# Adafruit_Bluefruit_LE_USB_Friend_Rev_I.net
KiCad netlist of a schematic drawn in EAGLE
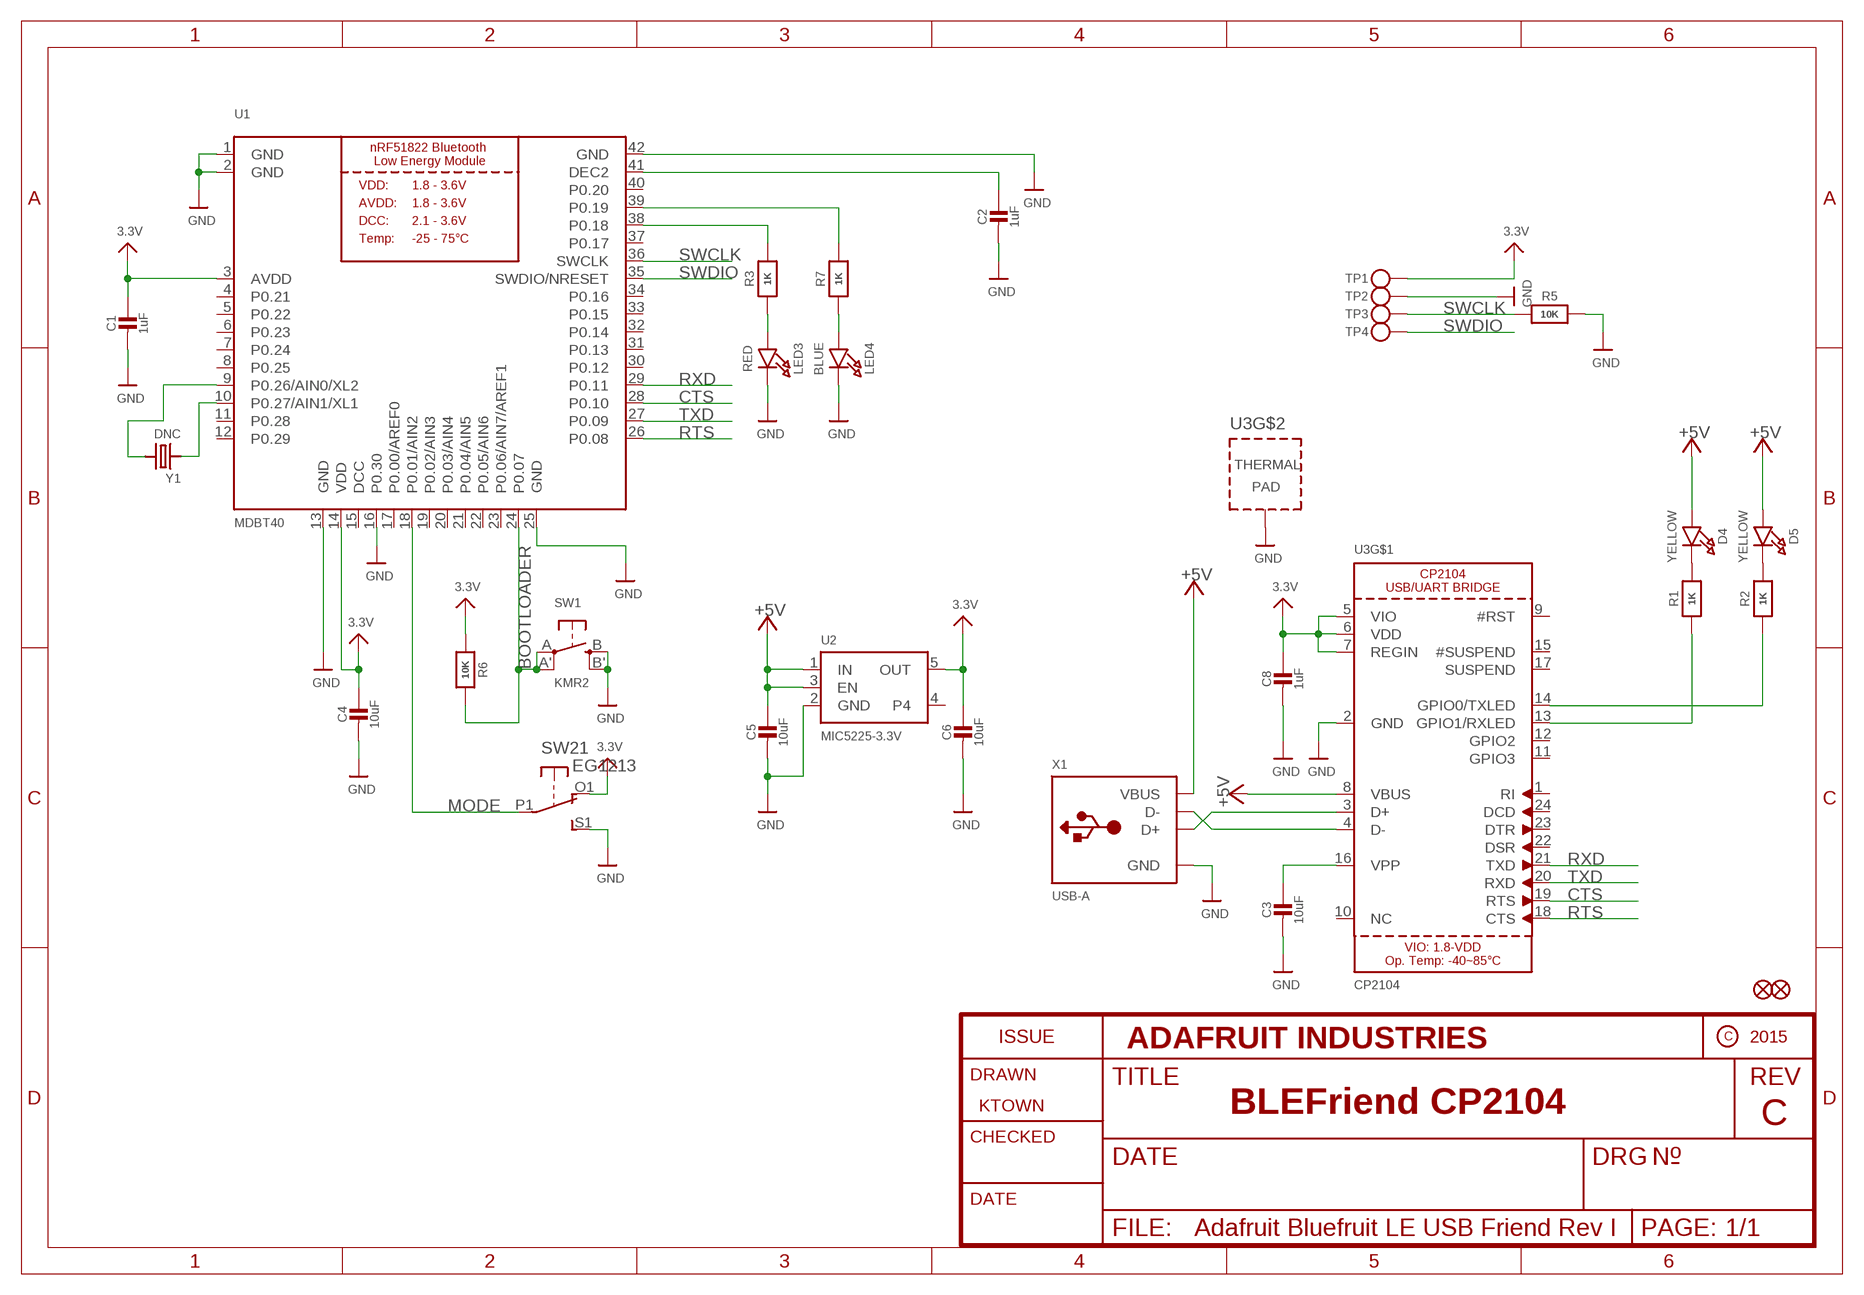
[diagram p0: schematic, sheet 1]

(export (version "E")
  (design (tool "Eeschema 10.0.6"))
  (components
    (comp (ref "C1")
      (value "1uF")
      (footprint "eagle-import:0805-NO")
      (libsource (lib "eagle-import") (part "CAP_CERAMIC0805-NOOUTLINE"))
    )
    (comp (ref "C2")
      (value "1uF")
      (footprint "eagle-import:0805-NO")
      (libsource (lib "eagle-import") (part "CAP_CERAMIC0805-NOOUTLINE"))
    )
    (comp (ref "C3")
      (value "10uF")
      (footprint "eagle-import:0805-NO")
      (libsource (lib "eagle-import") (part "CAP_CERAMIC0805-NOOUTLINE"))
    )
    (comp (ref "C4")
      (value "10uF")
      (footprint "eagle-import:0805-NO")
      (libsource (lib "eagle-import") (part "CAP_CERAMIC0805-NOOUTLINE"))
    )
    (comp (ref "C5")
      (value "10uF")
      (footprint "eagle-import:0805-NO")
      (libsource (lib "eagle-import") (part "CAP_CERAMIC0805-NOOUTLINE"))
    )
    (comp (ref "C6")
      (value "10uF")
      (footprint "eagle-import:0805-NO")
      (libsource (lib "eagle-import") (part "CAP_CERAMIC0805-NOOUTLINE"))
    )
    (comp (ref "C8")
      (value "1uF")
      (footprint "eagle-import:0805-NO")
      (libsource (lib "eagle-import") (part "CAP_CERAMIC0805-NOOUTLINE"))
    )
    (comp (ref "D4")
      (value "YELLOW")
      (footprint "eagle-import:CHIPLED_0805_NOOUTLINE")
      (libsource (lib "eagle-import") (part "LED0805_NOOUTLINE"))
    )
    (comp (ref "D5")
      (value "YELLOW")
      (footprint "eagle-import:CHIPLED_0805_NOOUTLINE")
      (libsource (lib "eagle-import") (part "LED0805_NOOUTLINE"))
    )
    (comp (ref "FID1")
      (value "FIDUCIAL\"\"")
      (footprint "eagle-import:FIDUCIAL_1MM")
      (libsource (lib "eagle-import") (part "FIDUCIAL{dblquote}{dblquote}"))
    )
    (comp (ref "FID2")
      (value "FIDUCIAL\"\"")
      (footprint "eagle-import:FIDUCIAL_1MM")
      (libsource (lib "eagle-import") (part "FIDUCIAL{dblquote}{dblquote}"))
    )
    (comp (ref "LED3")
      (value "RED")
      (footprint "eagle-import:CHIPLED_0805_NOOUTLINE")
      (libsource (lib "eagle-import") (part "LED0805_NOOUTLINE"))
    )
    (comp (ref "LED4")
      (value "BLUE")
      (footprint "eagle-import:CHIPLED_0805_NOOUTLINE")
      (libsource (lib "eagle-import") (part "LED0805_NOOUTLINE"))
    )
    (comp (ref "R1")
      (value "1K")
      (footprint "eagle-import:0805-NO")
      (libsource (lib "eagle-import") (part "RESISTOR0805_NOOUTLINE"))
    )
    (comp (ref "R2")
      (value "1K")
      (footprint "eagle-import:0805-NO")
      (libsource (lib "eagle-import") (part "RESISTOR0805_NOOUTLINE"))
    )
    (comp (ref "R3")
      (value "1K")
      (footprint "eagle-import:0805_10MGAP")
      (libsource (lib "eagle-import") (part "RESISTOR0805_10MGAP"))
    )
    (comp (ref "R5")
      (value "10K")
      (footprint "eagle-import:0805-NO")
      (libsource (lib "eagle-import") (part "RESISTOR0805_NOOUTLINE"))
    )
    (comp (ref "R6")
      (value "10K")
      (footprint "eagle-import:0805-NO")
      (libsource (lib "eagle-import") (part "RESISTOR0805_NOOUTLINE"))
    )
    (comp (ref "R7")
      (value "1K")
      (footprint "eagle-import:_0805MP")
      (libsource (lib "eagle-import") (part "RESISTOR_0805MP"))
    )
    (comp (ref "SW1")
      (value "KMR2")
      (footprint "eagle-import:BTN_KMR2_4.6X2.8")
      (libsource (lib "eagle-import") (part "SWITCH_TACT_SMT4.6X2.8"))
    )
    (comp (ref "SW2")
      (value "EG1213")
      (footprint "eagle-import:EG1390")
      (libsource (lib "eagle-import") (part "DPDT-EG1390"))
    )
    (comp (ref "TP1")
      (value "TESTPOINTROUND2MM")
      (footprint "eagle-import:TESTPOINT_ROUND_2MM")
      (libsource (lib "eagle-import") (part "TESTPOINTROUND2MM"))
    )
    (comp (ref "TP2")
      (value "TESTPOINTROUND2MM")
      (footprint "eagle-import:TESTPOINT_ROUND_2MM")
      (libsource (lib "eagle-import") (part "TESTPOINTROUND2MM"))
    )
    (comp (ref "TP3")
      (value "TESTPOINTROUND2MM")
      (footprint "eagle-import:TESTPOINT_ROUND_2MM")
      (libsource (lib "eagle-import") (part "TESTPOINTROUND2MM"))
    )
    (comp (ref "TP4")
      (value "TESTPOINTROUND2MM")
      (footprint "eagle-import:TESTPOINT_ROUND_2MM")
      (libsource (lib "eagle-import") (part "TESTPOINTROUND2MM"))
    )
    (comp (ref "U1")
      (value "MDBT40")
      (footprint "eagle-import:BLE_MODULE_RAYTAC_MDBT40")
      (libsource (lib "eagle-import") (part "BLE_MODULE_RAYTAC_MDBT40"))
    )
    (comp (ref "U2")
      (value "MIC5225-3.3V")
      (footprint "eagle-import:SOT23-5")
      (libsource (lib "eagle-import") (part "VREG_SOT23-5"))
    )
    (comp (ref "U3")
      (value "CP2104")
      (footprint "eagle-import:QFN24_4MM_SMSC")
      (libsource (lib "eagle-import") (part "CP2104"))
    )
    (comp (ref "X1")
      (value "USB-A")
      (footprint "eagle-import:USB_A-THM")
      (libsource (lib "eagle-import") (part "USB_TYPEA_CLIENTTHM"))
    )
    (comp (ref "Y1")
      (value "DNC")
      (footprint "eagle-import:CRYSTAL_CYL_2X6MM_SMT")
      (libsource (lib "eagle-import") (part "CRYSTAL2.0X6.0_32.768"))
    )
  )
  (nets
    (net (code "1") (name "+5V") (class "Default")
      (node (ref "C5") (pin "1") (pinfunction "1_1") (pintype "passive"))
      (node (ref "D4") (pin "A") (pinfunction "A_A") (pintype "passive"))
      (node (ref "D5") (pin "A") (pinfunction "A_A") (pintype "passive"))
      (node (ref "U2") (pin "1") (pinfunction "IN_1") (pintype "power_in"))
      (node (ref "U2") (pin "3") (pinfunction "EN_3") (pintype "input"))
      (node (ref "U3") (pin "8") (pinfunction "VBUS_8") (pintype "power_in"))
      (node (ref "X1") (pin "VBUS") (pinfunction "VBUS_VBUS") (pintype "power_in"))
    )
    (net (code "2") (name "/BOOTLOADER") (class "Default")
      (node (ref "R6") (pin "2") (pinfunction "2_2") (pintype "passive"))
      (node (ref "SW1") (pin "A") (pinfunction "P_A") (pintype "passive"))
      (node (ref "SW1") (pin "A'") (pinfunction "P1_A'") (pintype "passive"))
      (node (ref "U1") (pin "24") (pinfunction "P0.07_24") (pintype "bidirectional"))
    )
    (net (code "3") (name "/CTS") (class "Default")
      (node (ref "U1") (pin "28") (pinfunction "P0.10_28") (pintype "bidirectional"))
      (node (ref "U3") (pin "19") (pinfunction "RTS_19") (pintype "output"))
    )
    (net (code "4") (name "/DCC") (class "Default")
      (node (ref "U1") (pin "15") (pinfunction "DCC_15") (pintype "power_in"))
    )
    (net (code "5") (name "/MODE") (class "Default")
      (node (ref "SW2") (pin "P1") (pinfunction "P_P1") (pintype "passive"))
      (node (ref "U1") (pin "18") (pinfunction "P0.01/AIN2_18") (pintype "bidirectional"))
    )
    (net (code "6") (name "/RTS") (class "Default")
      (node (ref "U1") (pin "26") (pinfunction "P0.08_26") (pintype "bidirectional"))
      (node (ref "U3") (pin "18") (pinfunction "CTS_18") (pintype "input"))
    )
    (net (code "7") (name "/RXD") (class "Default")
      (node (ref "U1") (pin "29") (pinfunction "P0.11_29") (pintype "bidirectional"))
      (node (ref "U3") (pin "21") (pinfunction "TXD_21") (pintype "output"))
    )
    (net (code "8") (name "/SWCLK") (class "Default")
      (node (ref "R5") (pin "1") (pinfunction "1_1") (pintype "passive"))
      (node (ref "TP3") (pin "P$1") (pinfunction "P$1_P$1") (pintype "bidirectional"))
      (node (ref "U1") (pin "36") (pinfunction "SWCLK_36") (pintype "bidirectional"))
    )
    (net (code "9") (name "/SWDIO") (class "Default")
      (node (ref "TP4") (pin "P$1") (pinfunction "P$1_P$1") (pintype "bidirectional"))
      (node (ref "U1") (pin "35") (pinfunction "SWDIO/NRESET_35") (pintype "bidirectional"))
    )
    (net (code "10") (name "/TXD") (class "Default")
      (node (ref "U1") (pin "27") (pinfunction "P0.09_27") (pintype "bidirectional"))
      (node (ref "U3") (pin "20") (pinfunction "RXD_20") (pintype "input"))
    )
    (net (code "11") (name "3.3V") (class "Default")
      (node (ref "C1") (pin "1") (pinfunction "1_1") (pintype "passive"))
      (node (ref "C4") (pin "1") (pinfunction "1_1") (pintype "passive"))
      (node (ref "C6") (pin "1") (pinfunction "1_1") (pintype "passive"))
      (node (ref "C8") (pin "1") (pinfunction "1_1") (pintype "passive"))
      (node (ref "R6") (pin "1") (pinfunction "1_1") (pintype "passive"))
      (node (ref "SW2") (pin "O1") (pinfunction "O_O1") (pintype "passive"))
      (node (ref "TP1") (pin "P$1") (pinfunction "P$1_P$1") (pintype "bidirectional"))
      (node (ref "U1") (pin "14") (pinfunction "VDD_14") (pintype "power_in"))
      (node (ref "U1") (pin "3") (pinfunction "AVDD_3") (pintype "power_in"))
      (node (ref "U2") (pin "5") (pinfunction "OUT_5") (pintype "power_in"))
      (node (ref "U3") (pin "5") (pinfunction "VIO_5") (pintype "power_in"))
      (node (ref "U3") (pin "6") (pinfunction "VDD_6") (pintype "power_in"))
      (node (ref "U3") (pin "7") (pinfunction "REGIN_7") (pintype "power_in"))
    )
    (net (code "12") (name "GND") (class "Default")
      (node (ref "C1") (pin "2") (pinfunction "2_2") (pintype "passive"))
      (node (ref "C2") (pin "2") (pinfunction "2_2") (pintype "passive"))
      (node (ref "C3") (pin "2") (pinfunction "2_2") (pintype "passive"))
      (node (ref "C4") (pin "2") (pinfunction "2_2") (pintype "passive"))
      (node (ref "C5") (pin "2") (pinfunction "2_2") (pintype "passive"))
      (node (ref "C6") (pin "2") (pinfunction "2_2") (pintype "passive"))
      (node (ref "C8") (pin "2") (pinfunction "2_2") (pintype "passive"))
      (node (ref "LED3") (pin "C") (pinfunction "C_C") (pintype "passive"))
      (node (ref "LED4") (pin "C") (pinfunction "C_C") (pintype "passive"))
      (node (ref "R5") (pin "2") (pinfunction "2_2") (pintype "passive"))
      (node (ref "SW1") (pin "B") (pinfunction "S_B") (pintype "passive"))
      (node (ref "SW1") (pin "B'") (pinfunction "S1_B'") (pintype "passive"))
      (node (ref "SW2") (pin "S1") (pinfunction "S_S1") (pintype "passive"))
      (node (ref "TP2") (pin "P$1") (pinfunction "P$1_P$1") (pintype "bidirectional"))
      (node (ref "U1") (pin "1") (pinfunction "GND_1") (pintype "power_in"))
      (node (ref "U1") (pin "13") (pinfunction "GND_13") (pintype "power_in"))
      (node (ref "U1") (pin "16") (pinfunction "P0.30_16") (pintype "bidirectional"))
      (node (ref "U1") (pin "2") (pinfunction "GND_2") (pintype "power_in"))
      (node (ref "U1") (pin "25") (pinfunction "GND_25") (pintype "power_in"))
      (node (ref "U1") (pin "42") (pinfunction "GND_42") (pintype "power_in"))
      (node (ref "U2") (pin "2") (pinfunction "GND_2") (pintype "power_in"))
      (node (ref "U3") (pin "2") (pinfunction "GND_2") (pintype "power_in"))
      (node (ref "U3") (pin "THERM") (pinfunction "TP_THERM") (pintype "power_in"))
      (node (ref "X1") (pin "GND") (pinfunction "GND_GND") (pintype "power_in"))
    )
    (net (code "13") (name "Net-(D4-PadC)") (class "Default")
      (node (ref "D4") (pin "C") (pinfunction "C_C") (pintype "passive"))
      (node (ref "R1") (pin "2") (pinfunction "2_2") (pintype "passive"))
    )
    (net (code "14") (name "Net-(D5-PadC)") (class "Default")
      (node (ref "D5") (pin "C") (pinfunction "C_C") (pintype "passive"))
      (node (ref "R2") (pin "2") (pinfunction "2_2") (pintype "passive"))
    )
    (net (code "15") (name "Net-(LED3-PadA)") (class "Default")
      (node (ref "LED3") (pin "A") (pinfunction "A_A") (pintype "passive"))
      (node (ref "R3") (pin "1") (pinfunction "1_1") (pintype "passive"))
    )
    (net (code "16") (name "Net-(LED4-PadA)") (class "Default")
      (node (ref "LED4") (pin "A") (pinfunction "A_A") (pintype "passive"))
      (node (ref "R7") (pin "1") (pinfunction "1_1") (pintype "passive"))
    )
    (net (code "17") (name "Net-(U1-DEC2)") (class "Default")
      (node (ref "C2") (pin "1") (pinfunction "1_1") (pintype "passive"))
      (node (ref "U1") (pin "41") (pinfunction "DEC2_41") (pintype "power_in"))
    )
    (net (code "18") (name "Net-(U1-P0.18)") (class "Default")
      (node (ref "R3") (pin "2") (pinfunction "2_2") (pintype "passive"))
      (node (ref "U1") (pin "38") (pinfunction "P0.18_38") (pintype "bidirectional"))
    )
    (net (code "19") (name "Net-(U1-P0.19)") (class "Default")
      (node (ref "R7") (pin "2") (pinfunction "2_2") (pintype "passive"))
      (node (ref "U1") (pin "39") (pinfunction "P0.19_39") (pintype "bidirectional"))
    )
    (net (code "20") (name "Net-(U1-P0.26{slash}AIN0{slash}XL2)") (class "Default")
      (node (ref "U1") (pin "9") (pinfunction "P0.26/AIN0/XL2_9") (pintype "bidirectional"))
      (node (ref "Y1") (pin "2") (pinfunction "2_2") (pintype "passive"))
    )
    (net (code "21") (name "Net-(U1-P0.27{slash}AIN1{slash}XL1)") (class "Default")
      (node (ref "U1") (pin "10") (pinfunction "P0.27/AIN1/XL1_10") (pintype "bidirectional"))
      (node (ref "Y1") (pin "1") (pinfunction "1_1") (pintype "passive"))
    )
    (net (code "22") (name "Net-(U3A-D+)") (class "Default")
      (node (ref "U3") (pin "3") (pinfunction "D+_3") (pintype "bidirectional"))
      (node (ref "X1") (pin "D+") (pinfunction "D+_D+") (pintype "bidirectional"))
    )
    (net (code "23") (name "Net-(U3A-D-)") (class "Default")
      (node (ref "U3") (pin "4") (pinfunction "D-_4") (pintype "bidirectional"))
      (node (ref "X1") (pin "D-") (pinfunction "D-_D-") (pintype "bidirectional"))
    )
    (net (code "24") (name "Net-(U3A-GPIO0{slash}TXLED)") (class "Default")
      (node (ref "R2") (pin "1") (pinfunction "1_1") (pintype "passive"))
      (node (ref "U3") (pin "14") (pinfunction "GPIO0/TXLED_14") (pintype "bidirectional"))
    )
    (net (code "25") (name "Net-(U3A-GPIO1{slash}RXLED)") (class "Default")
      (node (ref "R1") (pin "1") (pinfunction "1_1") (pintype "passive"))
      (node (ref "U3") (pin "13") (pinfunction "GPIO1/RXLED_13") (pintype "bidirectional"))
    )
    (net (code "26") (name "Net-(U3A-VPP)") (class "Default")
      (node (ref "C3") (pin "1") (pinfunction "1_1") (pintype "passive"))
      (node (ref "U3") (pin "16") (pinfunction "VPP_16") (pintype "bidirectional"))
    )
    (net (code "27") (name "unconnected-(U1-P0.00{slash}AREF0-Pad17)") (class "Default")
      (node (ref "U1") (pin "17") (pinfunction "P0.00/AREF0_17") (pintype "bidirectional"))
    )
    (net (code "28") (name "unconnected-(U1-P0.02{slash}AIN3-Pad19)") (class "Default")
      (node (ref "U1") (pin "19") (pinfunction "P0.02/AIN3_19") (pintype "bidirectional"))
    )
    (net (code "29") (name "unconnected-(U1-P0.03{slash}AIN4-Pad20)") (class "Default")
      (node (ref "U1") (pin "20") (pinfunction "P0.03/AIN4_20") (pintype "bidirectional"))
    )
    (net (code "30") (name "unconnected-(U1-P0.04{slash}AIN5-Pad21)") (class "Default")
      (node (ref "U1") (pin "21") (pinfunction "P0.04/AIN5_21") (pintype "bidirectional"))
    )
    (net (code "31") (name "unconnected-(U1-P0.05{slash}AIN6-Pad22)") (class "Default")
      (node (ref "U1") (pin "22") (pinfunction "P0.05/AIN6_22") (pintype "bidirectional"))
    )
    (net (code "32") (name "unconnected-(U1-P0.06{slash}AIN7{slash}AREF1-Pad23)") (class "Default")
      (node (ref "U1") (pin "23") (pinfunction "P0.06/AIN7/AREF1_23") (pintype "bidirectional"))
    )
    (net (code "33") (name "unconnected-(U1-P0.12-Pad30)") (class "Default")
      (node (ref "U1") (pin "30") (pinfunction "P0.12_30") (pintype "bidirectional"))
    )
    (net (code "34") (name "unconnected-(U1-P0.13-Pad31)") (class "Default")
      (node (ref "U1") (pin "31") (pinfunction "P0.13_31") (pintype "bidirectional"))
    )
    (net (code "35") (name "unconnected-(U1-P0.14-Pad32)") (class "Default")
      (node (ref "U1") (pin "32") (pinfunction "P0.14_32") (pintype "bidirectional"))
    )
    (net (code "36") (name "unconnected-(U1-P0.15-Pad33)") (class "Default")
      (node (ref "U1") (pin "33") (pinfunction "P0.15_33") (pintype "bidirectional"))
    )
    (net (code "37") (name "unconnected-(U1-P0.16-Pad34)") (class "Default")
      (node (ref "U1") (pin "34") (pinfunction "P0.16_34") (pintype "bidirectional"))
    )
    (net (code "38") (name "unconnected-(U1-P0.17-Pad37)") (class "Default")
      (node (ref "U1") (pin "37") (pinfunction "P0.17_37") (pintype "bidirectional"))
    )
    (net (code "39") (name "unconnected-(U1-P0.20-Pad40)") (class "Default")
      (node (ref "U1") (pin "40") (pinfunction "P0.20_40") (pintype "bidirectional"))
    )
    (net (code "40") (name "unconnected-(U1-P0.21-Pad4)") (class "Default")
      (node (ref "U1") (pin "4") (pinfunction "P0.21_4") (pintype "bidirectional"))
    )
    (net (code "41") (name "unconnected-(U1-P0.22-Pad5)") (class "Default")
      (node (ref "U1") (pin "5") (pinfunction "P0.22_5") (pintype "bidirectional"))
    )
    (net (code "42") (name "unconnected-(U1-P0.23-Pad6)") (class "Default")
      (node (ref "U1") (pin "6") (pinfunction "P0.23_6") (pintype "bidirectional"))
    )
    (net (code "43") (name "unconnected-(U1-P0.24-Pad7)") (class "Default")
      (node (ref "U1") (pin "7") (pinfunction "P0.24_7") (pintype "bidirectional"))
    )
    (net (code "44") (name "unconnected-(U1-P0.25-Pad8)") (class "Default")
      (node (ref "U1") (pin "8") (pinfunction "P0.25_8") (pintype "bidirectional"))
    )
    (net (code "45") (name "unconnected-(U1-P0.28-Pad11)") (class "Default")
      (node (ref "U1") (pin "11") (pinfunction "P0.28_11") (pintype "bidirectional"))
    )
    (net (code "46") (name "unconnected-(U1-P0.29-Pad12)") (class "Default")
      (node (ref "U1") (pin "12") (pinfunction "P0.29_12") (pintype "bidirectional"))
    )
    (net (code "47") (name "unconnected-(U2-P4-Pad4)") (class "Default")
      (node (ref "U2") (pin "4") (pinfunction "P4_4") (pintype "bidirectional"))
    )
    (net (code "48") (name "unconnected-(U3A-#RST-Pad9)") (class "Default")
      (node (ref "U3") (pin "9") (pinfunction "#RST_9") (pintype "bidirectional"))
    )
    (net (code "49") (name "unconnected-(U3A-#SUSPEND-Pad15)") (class "Default")
      (node (ref "U3") (pin "15") (pinfunction "#SUSPEND_15") (pintype "output"))
    )
    (net (code "50") (name "unconnected-(U3A-DCD-Pad24)") (class "Default")
      (node (ref "U3") (pin "24") (pinfunction "DCD_24") (pintype "input"))
    )
    (net (code "51") (name "unconnected-(U3A-DSR-Pad22)") (class "Default")
      (node (ref "U3") (pin "22") (pinfunction "DSR_22") (pintype "input"))
    )
    (net (code "52") (name "unconnected-(U3A-DTR-Pad23)") (class "Default")
      (node (ref "U3") (pin "23") (pinfunction "DTR_23") (pintype "output"))
    )
    (net (code "53") (name "unconnected-(U3A-GPIO2-Pad12)") (class "Default")
      (node (ref "U3") (pin "12") (pinfunction "GPIO2_12") (pintype "bidirectional"))
    )
    (net (code "54") (name "unconnected-(U3A-GPIO3-Pad11)") (class "Default")
      (node (ref "U3") (pin "11") (pinfunction "GPIO3_11") (pintype "bidirectional"))
    )
    (net (code "55") (name "unconnected-(U3A-NC-Pad10)") (class "Default")
      (node (ref "U3") (pin "10") (pinfunction "NC_10") (pintype "no_connect"))
    )
    (net (code "56") (name "unconnected-(U3A-RI-Pad1)") (class "Default")
      (node (ref "U3") (pin "1") (pinfunction "RI_1") (pintype "input"))
    )
    (net (code "57") (name "unconnected-(U3A-SUSPEND-Pad17)") (class "Default")
      (node (ref "U3") (pin "17") (pinfunction "SUSPEND_17") (pintype "output"))
    )
  )
)
